# NFCaddonLStop_002.net
KiCad netlist of a schematic drawn in EAGLE
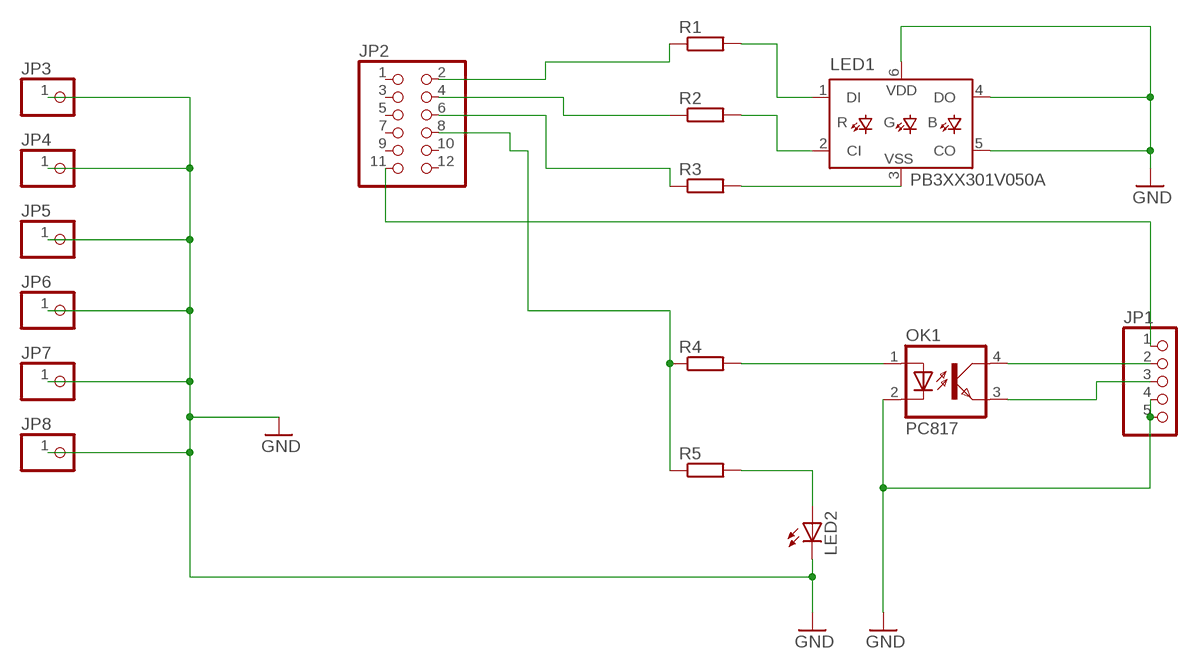
[diagram p0: schematic, sheet 1]

(export (version "E")
  (design (tool "Eeschema 10.0.6"))
  (components
    (comp (ref "JP1")
      (value "PINHD-1X5/90")
      (footprint "eagle-import:1X05_90")
      (libsource (lib "eagle-import") (part "PINHD-1X5/90"))
    )
    (comp (ref "JP2")
      (value "PINHD-2X6")
      (footprint "eagle-import:2X06")
      (libsource (lib "eagle-import") (part "PINHD-2X6"))
    )
    (comp (ref "JP3")
      (value "PINHD-1X1")
      (footprint "eagle-import:1X01")
      (libsource (lib "eagle-import") (part "PINHD-1X1"))
    )
    (comp (ref "JP4")
      (value "PINHD-1X1")
      (footprint "eagle-import:1X01")
      (libsource (lib "eagle-import") (part "PINHD-1X1"))
    )
    (comp (ref "JP5")
      (value "PINHD-1X1")
      (footprint "eagle-import:1X01")
      (libsource (lib "eagle-import") (part "PINHD-1X1"))
    )
    (comp (ref "JP6")
      (value "PINHD-1X1")
      (footprint "eagle-import:1X01")
      (libsource (lib "eagle-import") (part "PINHD-1X1"))
    )
    (comp (ref "JP7")
      (value "PINHD-1X1")
      (footprint "eagle-import:1X01")
      (libsource (lib "eagle-import") (part "PINHD-1X1"))
    )
    (comp (ref "JP8")
      (value "PINHD-1X1")
      (footprint "eagle-import:1X01")
      (libsource (lib "eagle-import") (part "PINHD-1X1"))
    )
    (comp (ref "LED1")
      (value "PB3XX301V050A")
      (footprint "eagle-import:PB3XX301V050A")
      (libsource (lib "eagle-import") (part "PB3XX301V050A"))
    )
    (comp (ref "LED2")
      (value "LEDCHIPLED_1206")
      (footprint "eagle-import:CHIPLED_1206")
      (libsource (lib "eagle-import") (part "LEDCHIPLED_1206"))
    )
    (comp (ref "OK1")
      (value "PC817")
      (footprint "eagle-import:DIL04")
      (fields (field (name "MPN") "PC817X4J000F"))
      (libsource (lib "eagle-import") (part "PC817"))
    )
    (comp (ref "R1")
      (value "R-EU_M1206")
      (footprint "eagle-import:M1206")
      (libsource (lib "eagle-import") (part "R-EU_M1206"))
    )
    (comp (ref "R2")
      (value "R-EU_M1206")
      (footprint "eagle-import:M1206")
      (libsource (lib "eagle-import") (part "R-EU_M1206"))
    )
    (comp (ref "R3")
      (value "R-EU_M1206")
      (footprint "eagle-import:M1206")
      (libsource (lib "eagle-import") (part "R-EU_M1206"))
    )
    (comp (ref "R4")
      (value "R-EU_M1206")
      (footprint "eagle-import:M1206")
      (libsource (lib "eagle-import") (part "R-EU_M1206"))
    )
    (comp (ref "R5")
      (value "R-EU_M1206")
      (footprint "eagle-import:M1206")
      (libsource (lib "eagle-import") (part "R-EU_M1206"))
    )
  )
  (nets
    (net (code "1") (name "GND") (class "Default")
      (node (ref "JP1") (pin "4") (pinfunction "4_4") (pintype "passive"))
      (node (ref "JP1") (pin "5") (pinfunction "5_5") (pintype "passive"))
      (node (ref "JP3") (pin "1") (pinfunction "1_1") (pintype "passive"))
      (node (ref "JP4") (pin "1") (pinfunction "1_1") (pintype "passive"))
      (node (ref "JP5") (pin "1") (pinfunction "1_1") (pintype "passive"))
      (node (ref "JP6") (pin "1") (pinfunction "1_1") (pintype "passive"))
      (node (ref "JP7") (pin "1") (pinfunction "1_1") (pintype "passive"))
      (node (ref "JP8") (pin "1") (pinfunction "1_1") (pintype "passive"))
      (node (ref "LED1") (pin "4") (pinfunction "DO_4") (pintype "output"))
      (node (ref "LED1") (pin "5") (pinfunction "CO_5") (pintype "output"))
      (node (ref "LED1") (pin "6") (pinfunction "VDD_6") (pintype "power_in"))
      (node (ref "LED2") (pin "C") (pinfunction "C_C") (pintype "passive"))
      (node (ref "OK1") (pin "2") (pinfunction "C_2") (pintype "passive"))
    )
    (net (code "2") (name "Net-(JP1-Pad1)") (class "Default")
      (node (ref "JP1") (pin "1") (pinfunction "1_1") (pintype "passive"))
      (node (ref "JP2") (pin "11") (pinfunction "11_11") (pintype "passive"))
    )
    (net (code "3") (name "Net-(JP2-Pad2)") (class "Default")
      (node (ref "JP2") (pin "2") (pinfunction "2_2") (pintype "passive"))
      (node (ref "R1") (pin "1") (pinfunction "1_1") (pintype "passive"))
    )
    (net (code "4") (name "Net-(JP2-Pad4)") (class "Default")
      (node (ref "JP2") (pin "4") (pinfunction "4_4") (pintype "passive"))
      (node (ref "R2") (pin "1") (pinfunction "1_1") (pintype "passive"))
    )
    (net (code "5") (name "Net-(JP2-Pad6)") (class "Default")
      (node (ref "JP2") (pin "6") (pinfunction "6_6") (pintype "passive"))
      (node (ref "R3") (pin "1") (pinfunction "1_1") (pintype "passive"))
    )
    (net (code "6") (name "Net-(JP2-Pad8)") (class "Default")
      (node (ref "JP2") (pin "8") (pinfunction "8_8") (pintype "passive"))
      (node (ref "R4") (pin "1") (pinfunction "1_1") (pintype "passive"))
      (node (ref "R5") (pin "1") (pinfunction "1_1") (pintype "passive"))
    )
    (net (code "7") (name "Net-(LED1-CI)") (class "Default")
      (node (ref "LED1") (pin "2") (pinfunction "CI_2") (pintype "input"))
      (node (ref "R2") (pin "2") (pinfunction "2_2") (pintype "passive"))
    )
    (net (code "8") (name "Net-(LED1-DI)") (class "Default")
      (node (ref "LED1") (pin "1") (pinfunction "DI_1") (pintype "input"))
      (node (ref "R1") (pin "2") (pinfunction "2_2") (pintype "passive"))
    )
    (net (code "9") (name "Net-(LED1-VSS)") (class "Default")
      (node (ref "LED1") (pin "3") (pinfunction "VSS_3") (pintype "power_in"))
      (node (ref "R3") (pin "2") (pinfunction "2_2") (pintype "passive"))
    )
    (net (code "10") (name "Net-(LED2-PadA)") (class "Default")
      (node (ref "LED2") (pin "A") (pinfunction "A_A") (pintype "passive"))
      (node (ref "R5") (pin "2") (pinfunction "2_2") (pintype "passive"))
    )
    (net (code "11") (name "Net-(OK1-A)") (class "Default")
      (node (ref "OK1") (pin "1") (pinfunction "A_1") (pintype "passive"))
      (node (ref "R4") (pin "2") (pinfunction "2_2") (pintype "passive"))
    )
    (net (code "12") (name "Net-(OK1-COL)") (class "Default")
      (node (ref "JP1") (pin "2") (pinfunction "2_2") (pintype "passive"))
      (node (ref "OK1") (pin "4") (pinfunction "COL_4") (pintype "passive"))
    )
    (net (code "13") (name "Net-(OK1-EMIT)") (class "Default")
      (node (ref "JP1") (pin "3") (pinfunction "3_3") (pintype "passive"))
      (node (ref "OK1") (pin "3") (pinfunction "EMIT_3") (pintype "passive"))
    )
    (net (code "14") (name "unconnected-(JP2-Pad1)") (class "Default")
      (node (ref "JP2") (pin "1") (pinfunction "1_1") (pintype "passive"))
    )
    (net (code "15") (name "unconnected-(JP2-Pad3)") (class "Default")
      (node (ref "JP2") (pin "3") (pinfunction "3_3") (pintype "passive"))
    )
    (net (code "16") (name "unconnected-(JP2-Pad5)") (class "Default")
      (node (ref "JP2") (pin "5") (pinfunction "5_5") (pintype "passive"))
    )
    (net (code "17") (name "unconnected-(JP2-Pad7)") (class "Default")
      (node (ref "JP2") (pin "7") (pinfunction "7_7") (pintype "passive"))
    )
    (net (code "18") (name "unconnected-(JP2-Pad9)") (class "Default")
      (node (ref "JP2") (pin "9") (pinfunction "9_9") (pintype "passive"))
    )
    (net (code "19") (name "unconnected-(JP2-Pad10)") (class "Default")
      (node (ref "JP2") (pin "10") (pinfunction "10_10") (pintype "passive"))
    )
    (net (code "20") (name "unconnected-(JP2-Pad12)") (class "Default")
      (node (ref "JP2") (pin "12") (pinfunction "12_12") (pintype "passive"))
    )
  )
)
